# KeyChaininoTHT.net
KiCad netlist of a schematic drawn in EAGLE
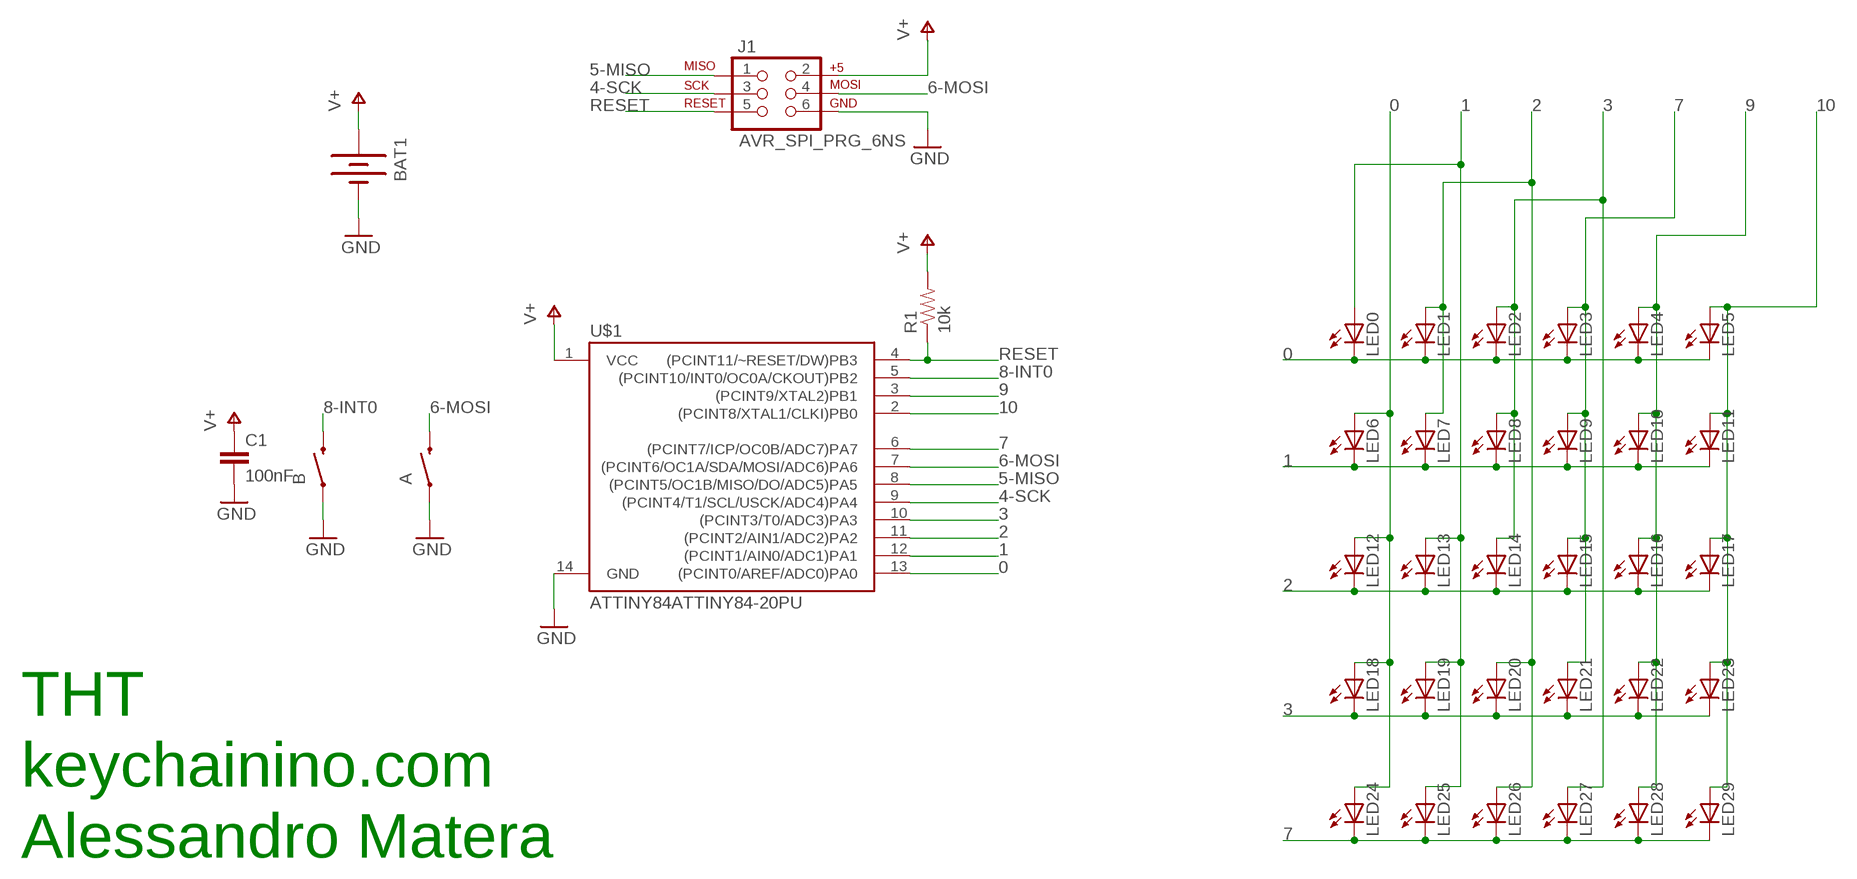
[diagram p0: schematic, sheet 1]

(export (version "E")
  (design (tool "Eeschema 10.0.6"))
  (components
    (comp (ref "A")
      (value "SWITCH-MOMENTARY-2PTH")
      (footprint "eagle-import:TACTILE-PTH")
      (libsource (lib "eagle-import") (part "SWITCH-MOMENTARY-2PTH"))
    )
    (comp (ref "B")
      (value "SWITCH-MOMENTARY-2PTH")
      (footprint "eagle-import:TACTILE-PTH")
      (libsource (lib "eagle-import") (part "SWITCH-MOMENTARY-2PTH"))
    )
    (comp (ref "BAT1")
      (value "BATTERY20PTH")
      (footprint "eagle-import:BATTCOM_20MM_PTH")
      (libsource (lib "eagle-import") (part "BATTERY20PTH"))
    )
    (comp (ref "C1")
      (value "100nF")
      (footprint "eagle-import:CAP-PTH-SMALL-KIT")
      (libsource (lib "eagle-import") (part "CAPKIT"))
    )
    (comp (ref "J1")
      (value "AVR_SPI_PRG_6NS")
      (footprint "eagle-import:2X3-NS")
      (libsource (lib "eagle-import") (part "AVR_SPI_PRG_6NS"))
    )
    (comp (ref "LED0")
      (value "LED3MM")
      (footprint "eagle-import:LED3MM")
      (libsource (lib "eagle-import") (part "LED3MM"))
    )
    (comp (ref "LED1")
      (value "LED3MM")
      (footprint "eagle-import:LED3MM")
      (libsource (lib "eagle-import") (part "LED3MM"))
    )
    (comp (ref "LED2")
      (value "LED3MM")
      (footprint "eagle-import:LED3MM")
      (libsource (lib "eagle-import") (part "LED3MM"))
    )
    (comp (ref "LED3")
      (value "LED3MM")
      (footprint "eagle-import:LED3MM")
      (libsource (lib "eagle-import") (part "LED3MM"))
    )
    (comp (ref "LED4")
      (value "LED3MM")
      (footprint "eagle-import:LED3MM")
      (libsource (lib "eagle-import") (part "LED3MM"))
    )
    (comp (ref "LED5")
      (value "LED3MM")
      (footprint "eagle-import:LED3MM")
      (libsource (lib "eagle-import") (part "LED3MM"))
    )
    (comp (ref "LED6")
      (value "LED3MM")
      (footprint "eagle-import:LED3MM")
      (libsource (lib "eagle-import") (part "LED3MM"))
    )
    (comp (ref "LED7")
      (value "LED3MM")
      (footprint "eagle-import:LED3MM")
      (libsource (lib "eagle-import") (part "LED3MM"))
    )
    (comp (ref "LED8")
      (value "LED3MM")
      (footprint "eagle-import:LED3MM")
      (libsource (lib "eagle-import") (part "LED3MM"))
    )
    (comp (ref "LED9")
      (value "LED3MM")
      (footprint "eagle-import:LED3MM")
      (libsource (lib "eagle-import") (part "LED3MM"))
    )
    (comp (ref "LED10")
      (value "LED3MM")
      (footprint "eagle-import:LED3MM")
      (libsource (lib "eagle-import") (part "LED3MM"))
    )
    (comp (ref "LED11")
      (value "LED3MM")
      (footprint "eagle-import:LED3MM")
      (libsource (lib "eagle-import") (part "LED3MM"))
    )
    (comp (ref "LED12")
      (value "LED3MM")
      (footprint "eagle-import:LED3MM")
      (libsource (lib "eagle-import") (part "LED3MM"))
    )
    (comp (ref "LED13")
      (value "LED3MM")
      (footprint "eagle-import:LED3MM")
      (libsource (lib "eagle-import") (part "LED3MM"))
    )
    (comp (ref "LED14")
      (value "LED3MM")
      (footprint "eagle-import:LED3MM")
      (libsource (lib "eagle-import") (part "LED3MM"))
    )
    (comp (ref "LED15")
      (value "LED3MM")
      (footprint "eagle-import:LED3MM")
      (libsource (lib "eagle-import") (part "LED3MM"))
    )
    (comp (ref "LED16")
      (value "LED3MM")
      (footprint "eagle-import:LED3MM")
      (libsource (lib "eagle-import") (part "LED3MM"))
    )
    (comp (ref "LED17")
      (value "LED3MM")
      (footprint "eagle-import:LED3MM")
      (libsource (lib "eagle-import") (part "LED3MM"))
    )
    (comp (ref "LED18")
      (value "LED3MM")
      (footprint "eagle-import:LED3MM")
      (libsource (lib "eagle-import") (part "LED3MM"))
    )
    (comp (ref "LED19")
      (value "LED3MM")
      (footprint "eagle-import:LED3MM")
      (libsource (lib "eagle-import") (part "LED3MM"))
    )
    (comp (ref "LED20")
      (value "LED3MM")
      (footprint "eagle-import:LED3MM")
      (libsource (lib "eagle-import") (part "LED3MM"))
    )
    (comp (ref "LED21")
      (value "LED3MM")
      (footprint "eagle-import:LED3MM")
      (libsource (lib "eagle-import") (part "LED3MM"))
    )
    (comp (ref "LED22")
      (value "LED3MM")
      (footprint "eagle-import:LED3MM")
      (libsource (lib "eagle-import") (part "LED3MM"))
    )
    (comp (ref "LED23")
      (value "LED3MM")
      (footprint "eagle-import:LED3MM")
      (libsource (lib "eagle-import") (part "LED3MM"))
    )
    (comp (ref "LED24")
      (value "LED3MM")
      (footprint "eagle-import:LED3MM")
      (libsource (lib "eagle-import") (part "LED3MM"))
    )
    (comp (ref "LED25")
      (value "LED3MM")
      (footprint "eagle-import:LED3MM")
      (libsource (lib "eagle-import") (part "LED3MM"))
    )
    (comp (ref "LED26")
      (value "LED3MM")
      (footprint "eagle-import:LED3MM")
      (libsource (lib "eagle-import") (part "LED3MM"))
    )
    (comp (ref "LED27")
      (value "LED3MM")
      (footprint "eagle-import:LED3MM")
      (libsource (lib "eagle-import") (part "LED3MM"))
    )
    (comp (ref "LED28")
      (value "LED3MM")
      (footprint "eagle-import:LED3MM")
      (libsource (lib "eagle-import") (part "LED3MM"))
    )
    (comp (ref "LED29")
      (value "LED3MM")
      (footprint "eagle-import:LED3MM")
      (libsource (lib "eagle-import") (part "LED3MM"))
    )
    (comp (ref "R1")
      (value "10k")
      (footprint "eagle-import:AXIAL-0.3-KIT")
      (libsource (lib "eagle-import") (part "RESISTORKIT"))
    )
    (comp (ref "U$1")
      (value "ATTINY84ATTINY84-20PU")
      (footprint "eagle-import:DIL14")
      (libsource (lib "eagle-import") (part "ATTINY84ATTINY84-20PU"))
    )
  )
  (nets
    (net (code "1") (name "/0") (class "Default")
      (node (ref "LED0") (pin "K") (pinfunction "C_K") (pintype "passive"))
      (node (ref "LED1") (pin "K") (pinfunction "C_K") (pintype "passive"))
      (node (ref "LED12") (pin "A") (pinfunction "A_A") (pintype "passive"))
      (node (ref "LED18") (pin "A") (pinfunction "A_A") (pintype "passive"))
      (node (ref "LED2") (pin "K") (pinfunction "C_K") (pintype "passive"))
      (node (ref "LED24") (pin "A") (pinfunction "A_A") (pintype "passive"))
      (node (ref "LED3") (pin "K") (pinfunction "C_K") (pintype "passive"))
      (node (ref "LED4") (pin "K") (pinfunction "C_K") (pintype "passive"))
      (node (ref "LED5") (pin "K") (pinfunction "C_K") (pintype "passive"))
      (node (ref "LED6") (pin "A") (pinfunction "A_A") (pintype "passive"))
      (node (ref "U$1") (pin "13") (pinfunction "(PCINT0/AREF/ADC0)PA0_13") (pintype "bidirectional"))
    )
    (net (code "2") (name "/1") (class "Default")
      (node (ref "LED0") (pin "A") (pinfunction "A_A") (pintype "passive"))
      (node (ref "LED10") (pin "K") (pinfunction "C_K") (pintype "passive"))
      (node (ref "LED11") (pin "K") (pinfunction "C_K") (pintype "passive"))
      (node (ref "LED13") (pin "A") (pinfunction "A_A") (pintype "passive"))
      (node (ref "LED19") (pin "A") (pinfunction "A_A") (pintype "passive"))
      (node (ref "LED25") (pin "A") (pinfunction "A_A") (pintype "passive"))
      (node (ref "LED6") (pin "K") (pinfunction "C_K") (pintype "passive"))
      (node (ref "LED7") (pin "K") (pinfunction "C_K") (pintype "passive"))
      (node (ref "LED8") (pin "K") (pinfunction "C_K") (pintype "passive"))
      (node (ref "LED9") (pin "K") (pinfunction "C_K") (pintype "passive"))
      (node (ref "U$1") (pin "12") (pinfunction "(PCINT1/AIN0/ADC1)PA1_12") (pintype "bidirectional"))
    )
    (net (code "3") (name "/2") (class "Default")
      (node (ref "LED1") (pin "A") (pinfunction "A_A") (pintype "passive"))
      (node (ref "LED12") (pin "K") (pinfunction "C_K") (pintype "passive"))
      (node (ref "LED13") (pin "K") (pinfunction "C_K") (pintype "passive"))
      (node (ref "LED14") (pin "K") (pinfunction "C_K") (pintype "passive"))
      (node (ref "LED15") (pin "K") (pinfunction "C_K") (pintype "passive"))
      (node (ref "LED16") (pin "K") (pinfunction "C_K") (pintype "passive"))
      (node (ref "LED17") (pin "K") (pinfunction "C_K") (pintype "passive"))
      (node (ref "LED20") (pin "A") (pinfunction "A_A") (pintype "passive"))
      (node (ref "LED26") (pin "A") (pinfunction "A_A") (pintype "passive"))
      (node (ref "LED7") (pin "A") (pinfunction "A_A") (pintype "passive"))
      (node (ref "U$1") (pin "11") (pinfunction "(PCINT2/AIN1/ADC2)PA2_11") (pintype "bidirectional"))
    )
    (net (code "4") (name "/3") (class "Default")
      (node (ref "LED14") (pin "A") (pinfunction "A_A") (pintype "passive"))
      (node (ref "LED18") (pin "K") (pinfunction "C_K") (pintype "passive"))
      (node (ref "LED19") (pin "K") (pinfunction "C_K") (pintype "passive"))
      (node (ref "LED2") (pin "A") (pinfunction "A_A") (pintype "passive"))
      (node (ref "LED20") (pin "K") (pinfunction "C_K") (pintype "passive"))
      (node (ref "LED21") (pin "K") (pinfunction "C_K") (pintype "passive"))
      (node (ref "LED22") (pin "K") (pinfunction "C_K") (pintype "passive"))
      (node (ref "LED23") (pin "K") (pinfunction "C_K") (pintype "passive"))
      (node (ref "LED27") (pin "A") (pinfunction "A_A") (pintype "passive"))
      (node (ref "LED8") (pin "A") (pinfunction "A_A") (pintype "passive"))
      (node (ref "U$1") (pin "10") (pinfunction "(PCINT3/T0/ADC3)PA3_10") (pintype "bidirectional"))
    )
    (net (code "5") (name "/4-SCK") (class "Default")
      (node (ref "J1") (pin "3") (pinfunction "3_3") (pintype "passive"))
      (node (ref "U$1") (pin "9") (pinfunction "(PCINT4/T1/SCL/USCK/ADC4)PA4_9") (pintype "bidirectional"))
    )
    (net (code "6") (name "/5-MISO") (class "Default")
      (node (ref "J1") (pin "1") (pinfunction "1_1") (pintype "passive"))
      (node (ref "U$1") (pin "8") (pinfunction "(PCINT5/OC1B/MISO/DO/ADC5)PA5_8") (pintype "bidirectional"))
    )
    (net (code "7") (name "/6-MOSI") (class "Default")
      (node (ref "A") (pin "3") (pinfunction "2_3") (pintype "passive"))
      (node (ref "J1") (pin "4") (pinfunction "4_4") (pintype "passive"))
      (node (ref "U$1") (pin "7") (pinfunction "(PCINT6/OC1A/SDA/MOSI/ADC6)PA6_7") (pintype "bidirectional"))
    )
    (net (code "8") (name "/7") (class "Default")
      (node (ref "LED15") (pin "A") (pinfunction "A_A") (pintype "passive"))
      (node (ref "LED21") (pin "A") (pinfunction "A_A") (pintype "passive"))
      (node (ref "LED24") (pin "K") (pinfunction "C_K") (pintype "passive"))
      (node (ref "LED25") (pin "K") (pinfunction "C_K") (pintype "passive"))
      (node (ref "LED26") (pin "K") (pinfunction "C_K") (pintype "passive"))
      (node (ref "LED27") (pin "K") (pinfunction "C_K") (pintype "passive"))
      (node (ref "LED28") (pin "K") (pinfunction "C_K") (pintype "passive"))
      (node (ref "LED29") (pin "K") (pinfunction "C_K") (pintype "passive"))
      (node (ref "LED3") (pin "A") (pinfunction "A_A") (pintype "passive"))
      (node (ref "LED9") (pin "A") (pinfunction "A_A") (pintype "passive"))
      (node (ref "U$1") (pin "6") (pinfunction "(PCINT7/ICP/OC0B/ADC7)PA7_6") (pintype "bidirectional"))
    )
    (net (code "9") (name "/8-INT0") (class "Default")
      (node (ref "B") (pin "3") (pinfunction "2_3") (pintype "passive"))
      (node (ref "U$1") (pin "5") (pinfunction "(PCINT10/INT0/OC0A/CKOUT)PB2_5") (pintype "bidirectional"))
    )
    (net (code "10") (name "/9") (class "Default")
      (node (ref "LED10") (pin "A") (pinfunction "A_A") (pintype "passive"))
      (node (ref "LED16") (pin "A") (pinfunction "A_A") (pintype "passive"))
      (node (ref "LED22") (pin "A") (pinfunction "A_A") (pintype "passive"))
      (node (ref "LED28") (pin "A") (pinfunction "A_A") (pintype "passive"))
      (node (ref "LED4") (pin "A") (pinfunction "A_A") (pintype "passive"))
      (node (ref "U$1") (pin "3") (pinfunction "(PCINT9/XTAL2)PB1_3") (pintype "bidirectional"))
    )
    (net (code "11") (name "/10") (class "Default")
      (node (ref "LED11") (pin "A") (pinfunction "A_A") (pintype "passive"))
      (node (ref "LED17") (pin "A") (pinfunction "A_A") (pintype "passive"))
      (node (ref "LED23") (pin "A") (pinfunction "A_A") (pintype "passive"))
      (node (ref "LED29") (pin "A") (pinfunction "A_A") (pintype "passive"))
      (node (ref "LED5") (pin "A") (pinfunction "A_A") (pintype "passive"))
      (node (ref "U$1") (pin "2") (pinfunction "(PCINT8/XTAL1/CLKI)PB0_2") (pintype "bidirectional"))
    )
    (net (code "12") (name "/RESET") (class "Default")
      (node (ref "J1") (pin "5") (pinfunction "5_5") (pintype "passive"))
      (node (ref "R1") (pin "P$1") (pinfunction "1_P$1") (pintype "passive"))
      (node (ref "U$1") (pin "4") (pinfunction "(PCINT11/~{RESET/DW})PB3_4") (pintype "bidirectional"))
    )
    (net (code "13") (name "GND") (class "Default")
      (node (ref "A") (pin "1") (pinfunction "1_1") (pintype "passive"))
      (node (ref "B") (pin "1") (pinfunction "1_1") (pintype "passive"))
      (node (ref "BAT1") (pin "2") (pinfunction "-_2") (pintype "power_in"))
      (node (ref "C1") (pin "2") (pinfunction "2_2") (pintype "passive"))
      (node (ref "J1") (pin "6") (pinfunction "6_6") (pintype "passive"))
      (node (ref "U$1") (pin "14") (pinfunction "GND_14") (pintype "bidirectional"))
    )
    (net (code "14") (name "V+") (class "Default")
      (node (ref "BAT1") (pin "1") (pinfunction "+_1") (pintype "power_in"))
      (node (ref "C1") (pin "1") (pinfunction "1_1") (pintype "passive"))
      (node (ref "J1") (pin "2") (pinfunction "2_2") (pintype "passive"))
      (node (ref "R1") (pin "P$2") (pinfunction "2_P$2") (pintype "passive"))
      (node (ref "U$1") (pin "1") (pinfunction "VCC_1") (pintype "bidirectional"))
    )
  )
)
